# panel446.net
KiCad netlist of a schematic drawn in EAGLE
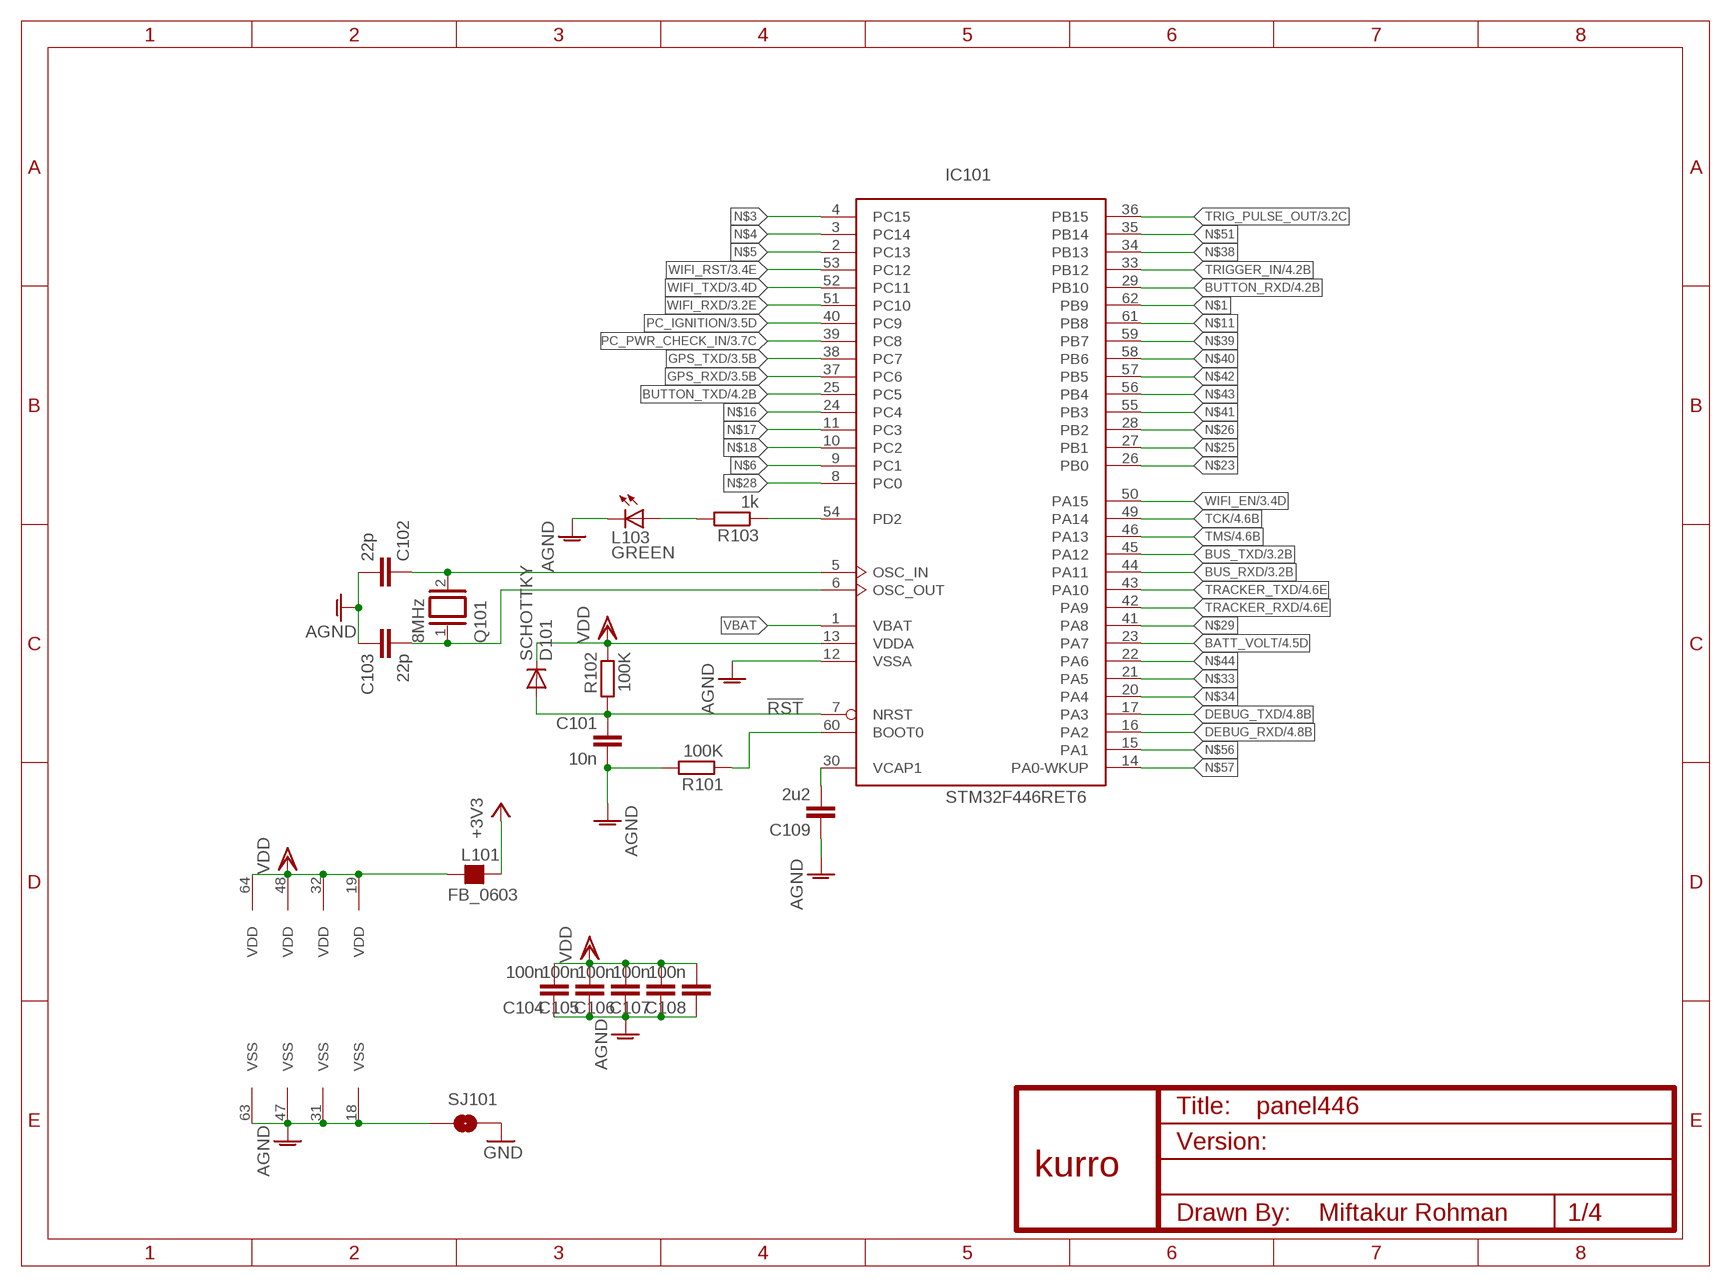
[diagram p0: schematic, sheet 1]
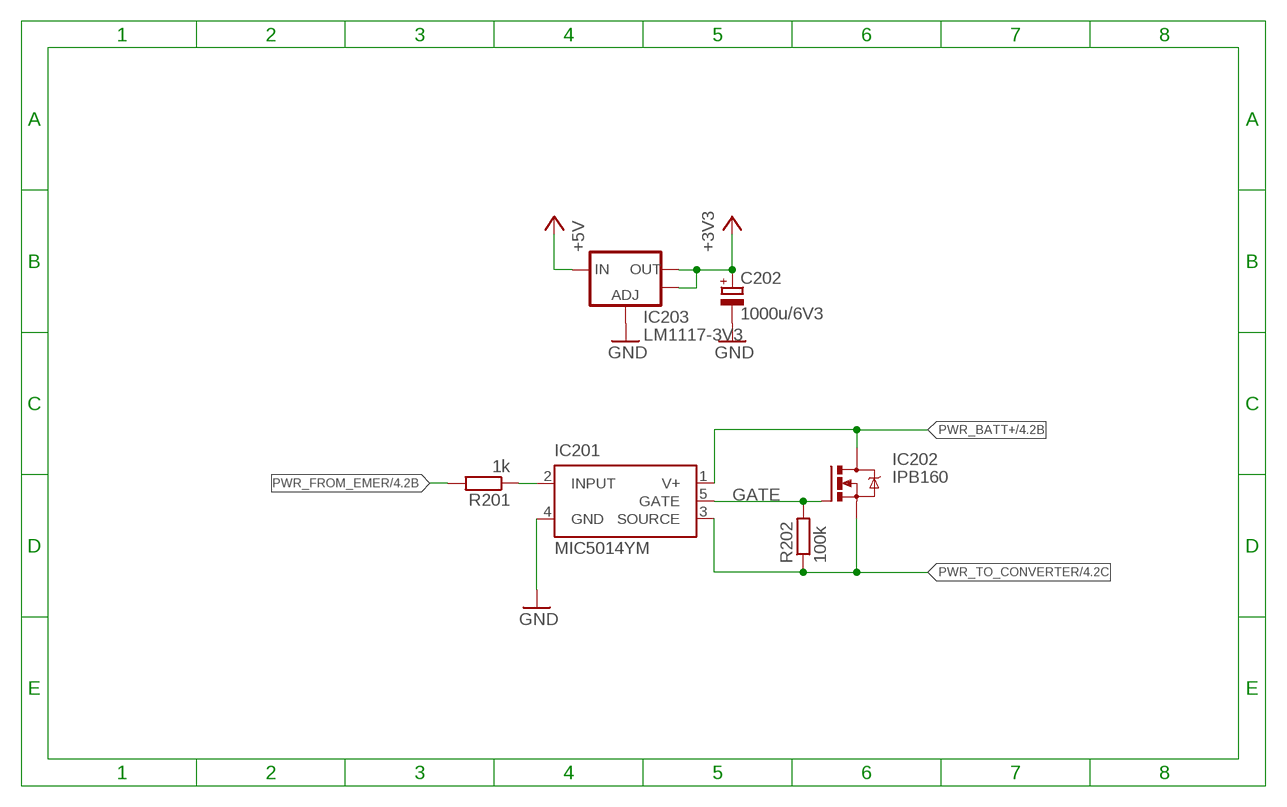
[diagram p1: schematic, sheet 2]
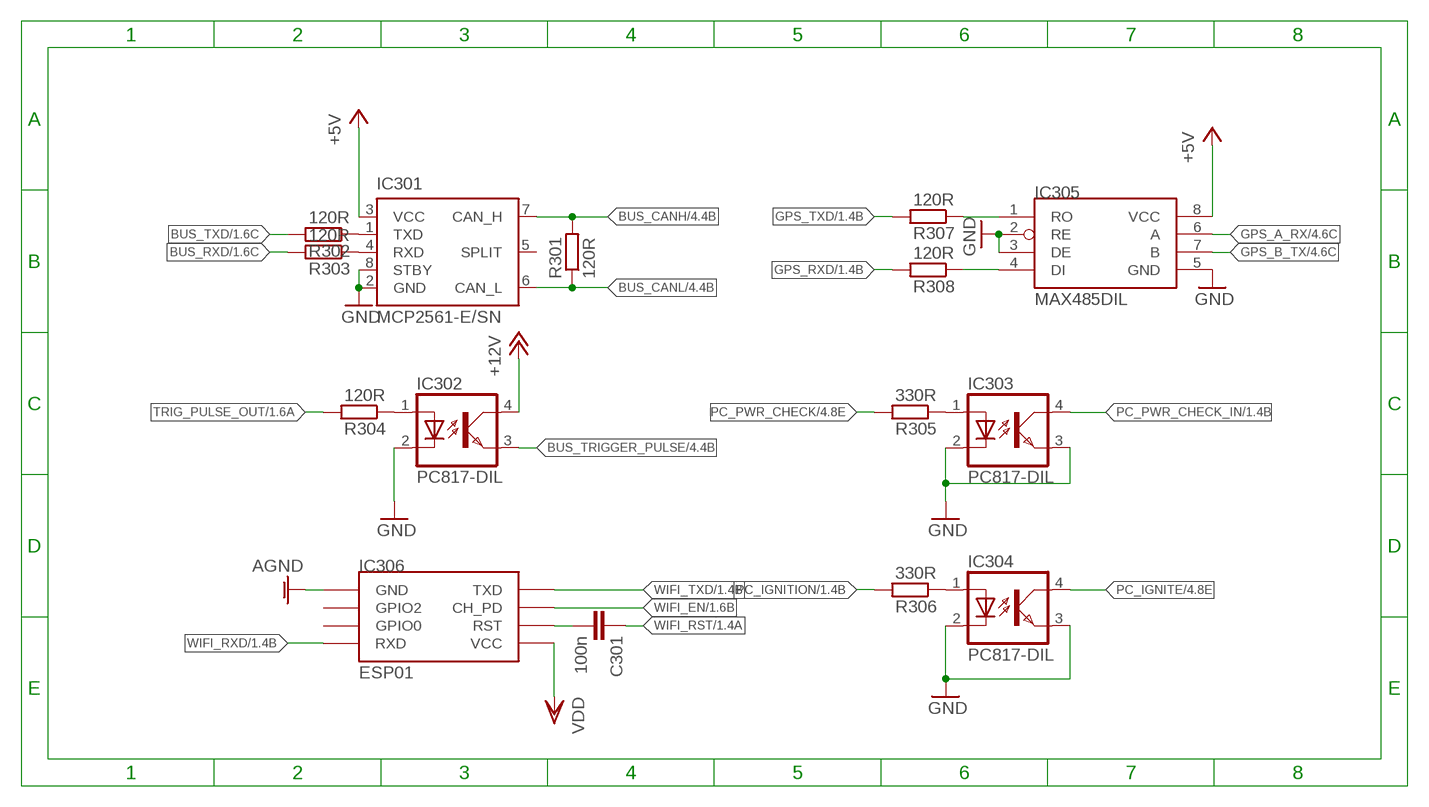
[diagram p2: schematic, sheet 3]
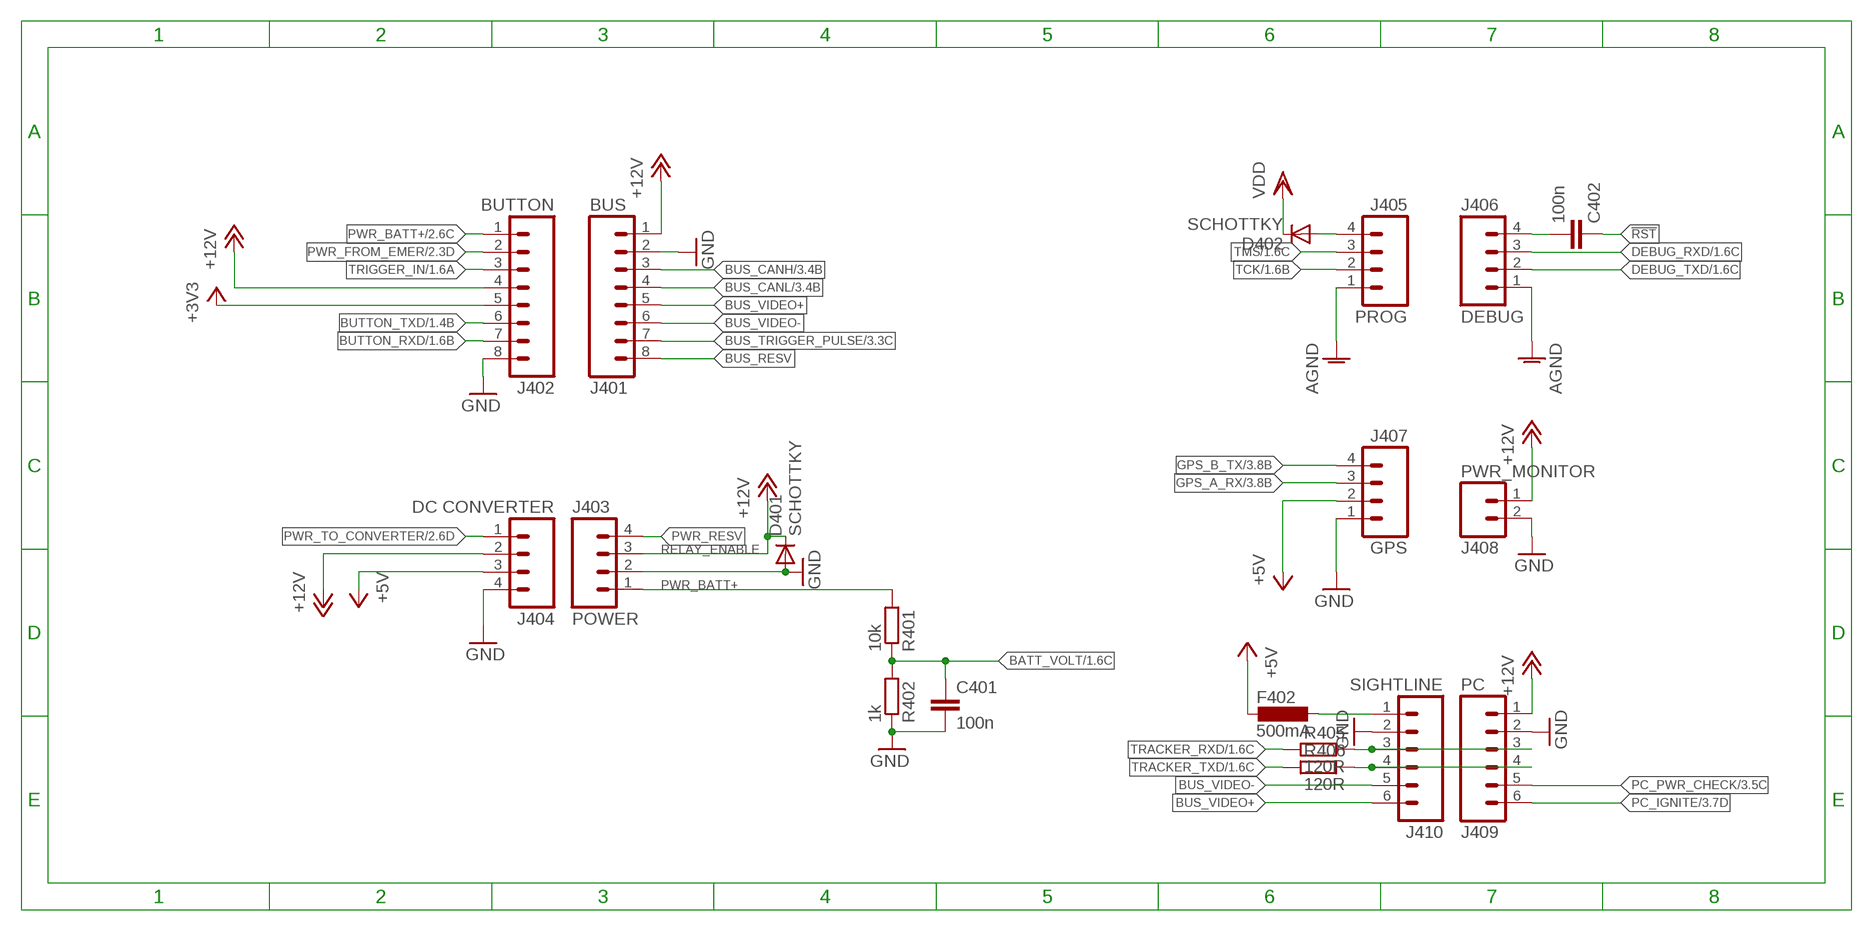
[diagram p3: schematic, sheet 4]

(export (version "E")
  (design (tool "Eeschema 10.0.6"))
  (components
    (comp (ref "C101")
      (value "10n")
      (footprint "eagle-import:C0603")
      (libsource (lib "eagle-import") (part "resistor_C-EUC0603"))
    )
    (comp (ref "C102")
      (value "22p")
      (footprint "eagle-import:C0603")
      (libsource (lib "eagle-import") (part "resistor_C-EUC0603"))
    )
    (comp (ref "C103")
      (value "22p")
      (footprint "eagle-import:C0603")
      (libsource (lib "eagle-import") (part "resistor_C-EUC0603"))
    )
    (comp (ref "C104")
      (value "100n")
      (footprint "eagle-import:C0603")
      (libsource (lib "eagle-import") (part "resistor_C-EUC0603"))
    )
    (comp (ref "C105")
      (value "100n")
      (footprint "eagle-import:C0603")
      (libsource (lib "eagle-import") (part "resistor_C-EUC0603"))
    )
    (comp (ref "C106")
      (value "100n")
      (footprint "eagle-import:C0603")
      (libsource (lib "eagle-import") (part "resistor_C-EUC0603"))
    )
    (comp (ref "C107")
      (value "100n")
      (footprint "eagle-import:C0603")
      (libsource (lib "eagle-import") (part "resistor_C-EUC0603"))
    )
    (comp (ref "C108")
      (value "100n")
      (footprint "eagle-import:C0603")
      (libsource (lib "eagle-import") (part "resistor_C-EUC0603"))
    )
    (comp (ref "C109")
      (value "2u2")
      (footprint "eagle-import:C0805")
      (libsource (lib "eagle-import") (part "C-EUC0805"))
    )
    (comp (ref "D101")
      (value "SCHOTTKY")
      (footprint "eagle-import:MICROMELF-W")
      (libsource (lib "eagle-import") (part "DIODE-MICROMELF-W"))
    )
    (comp (ref "IC101")
      (value "STM32F446RET6")
      (footprint "eagle-import:LQFP64")
      (libsource (lib "eagle-import") (part "STM32F401RTB"))
    )
    (comp (ref "L101")
      (value "FB_0603")
      (footprint "eagle-import:L0603")
      (libsource (lib "eagle-import") (part "FB_0603"))
    )
    (comp (ref "L103")
      (value "GREEN")
      (footprint "eagle-import:CHIP-LED0805")
      (libsource (lib "eagle-import") (part "LEDCHIP-LED0805"))
    )
    (comp (ref "Q101")
      (value "8MHz")
      (footprint "eagle-import:QS")
      (libsource (lib "eagle-import") (part "XTAL/S"))
    )
    (comp (ref "R101")
      (value "100K")
      (footprint "eagle-import:R0603")
      (libsource (lib "eagle-import") (part "resistor_R-EU_R0603"))
    )
    (comp (ref "R102")
      (value "100K")
      (footprint "eagle-import:R0603")
      (libsource (lib "eagle-import") (part "resistor_R-EU_R0603"))
    )
    (comp (ref "R103")
      (value "1k")
      (footprint "eagle-import:R0603")
      (libsource (lib "eagle-import") (part "resistor_R-EU_R0603"))
    )
    (comp (ref "SJ101")
      (value "SOLDERJUMPERTRACE")
      (footprint "eagle-import:SJ_2S-TRACE")
      (libsource (lib "eagle-import") (part "SOLDERJUMPERTRACE"))
    )
    (comp (ref "U$1")
      (value "KURRO_FOOTPRINT")
      (footprint "eagle-import:KURRO-LOGO")
      (libsource (lib "eagle-import") (part "KURRO_FOOTPRINT"))
    )
    (comp (ref "C202")
      (value "1000u/6V3")
      (footprint "eagle-import:153CLV-0810")
      (libsource (lib "eagle-import") (part "CPOL-EU153CLV-0810"))
    )
    (comp (ref "IC201")
      (value "MIC5014YM")
      (footprint "eagle-import:SO-08")
      (libsource (lib "eagle-import") (part "MIC501M4Y"))
    )
    (comp (ref "IC202")
      (value "IPB160")
      (footprint "eagle-import:PG-TO263-7")
      (libsource (lib "eagle-import") (part "IPB160"))
    )
    (comp (ref "IC203")
      (value "LM1117-3V3")
      (footprint "eagle-import:SOT223")
      (libsource (lib "eagle-import") (part "V_REG_LM1117SOT223"))
    )
    (comp (ref "R201")
      (value "1k")
      (footprint "eagle-import:R0603")
      (libsource (lib "eagle-import") (part "R-EU_R0603"))
    )
    (comp (ref "R202")
      (value "100k")
      (footprint "eagle-import:R0603")
      (libsource (lib "eagle-import") (part "R-EU_R0603"))
    )
    (comp (ref "C301")
      (value "100n")
      (footprint "eagle-import:C0603")
      (libsource (lib "eagle-import") (part "resistor_C-EUC0603"))
    )
    (comp (ref "IC301")
      (value "MCP2561-E/SN")
      (footprint "eagle-import:SOIC-8")
      (libsource (lib "eagle-import") (part "MCP2561-E/SN"))
    )
    (comp (ref "IC302")
      (value "PC817-DIL")
      (footprint "eagle-import:DIL04A")
      (libsource (lib "eagle-import") (part "PC817-DIL"))
    )
    (comp (ref "IC303")
      (value "PC817-DIL")
      (footprint "eagle-import:DIL04A")
      (libsource (lib "eagle-import") (part "PC817-DIL"))
    )
    (comp (ref "IC304")
      (value "PC817-DIL")
      (footprint "eagle-import:DIL04A")
      (libsource (lib "eagle-import") (part "PC817-DIL"))
    )
    (comp (ref "IC305")
      (value "MAX485DIL")
      (footprint "eagle-import:DIL08")
      (libsource (lib "eagle-import") (part "MAX485DIL"))
    )
    (comp (ref "IC306")
      (value "ESP01")
      (footprint "eagle-import:ESP01")
      (libsource (lib "eagle-import") (part "ESP01"))
    )
    (comp (ref "R301")
      (value "120R")
      (footprint "eagle-import:R0603")
      (libsource (lib "eagle-import") (part "R-EU_R0603"))
    )
    (comp (ref "R302")
      (value "120R")
      (footprint "eagle-import:R0603")
      (libsource (lib "eagle-import") (part "R-EU_R0603"))
    )
    (comp (ref "R303")
      (value "120R")
      (footprint "eagle-import:R0603")
      (libsource (lib "eagle-import") (part "R-EU_R0603"))
    )
    (comp (ref "R304")
      (value "120R")
      (footprint "eagle-import:R0603")
      (libsource (lib "eagle-import") (part "R-EU_R0603"))
    )
    (comp (ref "R305")
      (value "330R")
      (footprint "eagle-import:R0603")
      (libsource (lib "eagle-import") (part "R-EU_R0603"))
    )
    (comp (ref "R306")
      (value "330R")
      (footprint "eagle-import:R0603")
      (libsource (lib "eagle-import") (part "R-EU_R0603"))
    )
    (comp (ref "R307")
      (value "120R")
      (footprint "eagle-import:R0603")
      (libsource (lib "eagle-import") (part "R-EU_R0603"))
    )
    (comp (ref "R308")
      (value "120R")
      (footprint "eagle-import:R0603")
      (libsource (lib "eagle-import") (part "R-EU_R0603"))
    )
    (comp (ref "C401")
      (value "100n")
      (footprint "eagle-import:C0603")
      (libsource (lib "eagle-import") (part "resistor_C-EUC0603"))
    )
    (comp (ref "C402")
      (value "100n")
      (footprint "eagle-import:C0603")
      (libsource (lib "eagle-import") (part "resistor_C-EUC0603"))
    )
    (comp (ref "D401")
      (value "SCHOTTKY")
      (footprint "eagle-import:MICROMELF-W")
      (libsource (lib "eagle-import") (part "DIODE-MICROMELF-W"))
    )
    (comp (ref "D402")
      (value "SCHOTTKY")
      (footprint "eagle-import:MICROMELF-W")
      (libsource (lib "eagle-import") (part "DIODE-MICROMELF-W"))
    )
    (comp (ref "F402")
      (value "500mA")
      (footprint "eagle-import:L0805")
      (libsource (lib "eagle-import") (part "L-EUL0805"))
    )
    (comp (ref "J401")
      (value "BUS")
      (footprint "eagle-import:XH-8-VERT")
      (libsource (lib "eagle-import") (part "M08-XH-VERT"))
    )
    (comp (ref "J402")
      (value "BUTTON")
      (footprint "eagle-import:XH-8-VERT")
      (libsource (lib "eagle-import") (part "M08-XH-VERT"))
    )
    (comp (ref "J403")
      (value "POWER")
      (footprint "eagle-import:XH-4-VERT")
      (libsource (lib "eagle-import") (part "M04-XH-VERT"))
    )
    (comp (ref "J404")
      (value "DC CONVERTER")
      (footprint "eagle-import:XH-4-VERT")
      (libsource (lib "eagle-import") (part "M04-XH-VERT"))
    )
    (comp (ref "J405")
      (value "PROG")
      (footprint "eagle-import:XH-4-VERT")
      (libsource (lib "eagle-import") (part "M04-XH-VERT"))
    )
    (comp (ref "J406")
      (value "DEBUG")
      (footprint "eagle-import:XH-4-VERT")
      (libsource (lib "eagle-import") (part "M04-XH-VERT"))
    )
    (comp (ref "J407")
      (value "GPS")
      (footprint "eagle-import:XH-4-VERT")
      (libsource (lib "eagle-import") (part "M04-XH-VERT"))
    )
    (comp (ref "J408")
      (value "PWR_MONITOR")
      (footprint "eagle-import:XH-2-RA")
      (libsource (lib "eagle-import") (part "M02-XH-RA"))
    )
    (comp (ref "J409")
      (value "PC")
      (footprint "eagle-import:XH-6-VERT")
      (libsource (lib "eagle-import") (part "M06-XH-VERT"))
    )
    (comp (ref "J410")
      (value "SIGHTLINE")
      (footprint "eagle-import:XH-6-VERT")
      (libsource (lib "eagle-import") (part "M06-XH-VERT"))
    )
    (comp (ref "R401")
      (value "10k")
      (footprint "eagle-import:R0603")
      (libsource (lib "eagle-import") (part "R-EU_R0603"))
    )
    (comp (ref "R402")
      (value "1k")
      (footprint "eagle-import:R0603")
      (libsource (lib "eagle-import") (part "R-EU_R0603"))
    )
    (comp (ref "R405")
      (value "120R")
      (footprint "eagle-import:R0603")
      (libsource (lib "eagle-import") (part "R-EU_R0603"))
    )
    (comp (ref "R406")
      (value "120R")
      (footprint "eagle-import:R0603")
      (libsource (lib "eagle-import") (part "R-EU_R0603"))
    )
  )
  (nets
    (net (code "1") (name "+3V3") (class "Default")
      (node (ref "C202") (pin "+") (pinfunction "+_+") (pintype "passive"))
      (node (ref "IC203") (pin "2") (pinfunction "OUT_2") (pintype "power_in"))
      (node (ref "IC203") (pin "4") (pinfunction "OUT_4") (pintype "power_in"))
      (node (ref "J402") (pin "5") (pinfunction "5_5") (pintype "passive"))
      (node (ref "L101") (pin "2") (pinfunction "2_2") (pintype "passive"))
    )
    (net (code "2") (name "+5V") (class "Default")
      (node (ref "F402") (pin "2") (pinfunction "2_2") (pintype "passive"))
      (node (ref "IC203") (pin "3") (pinfunction "IN_3") (pintype "input"))
      (node (ref "IC301") (pin "3") (pinfunction "VCC_3") (pintype "bidirectional"))
      (node (ref "IC305") (pin "8") (pinfunction "VCC_8") (pintype "bidirectional"))
      (node (ref "J404") (pin "3") (pinfunction "3_3") (pintype "passive"))
      (node (ref "J407") (pin "2") (pinfunction "2_2") (pintype "passive"))
    )
    (net (code "3") (name "+12V") (class "Default")
      (node (ref "D401") (pin "C") (pinfunction "C_C") (pintype "passive"))
      (node (ref "IC302") (pin "4") (pinfunction "COL_4") (pintype "passive"))
      (node (ref "J401") (pin "1") (pinfunction "1_1") (pintype "passive"))
      (node (ref "J402") (pin "4") (pinfunction "4_4") (pintype "passive"))
      (node (ref "J403") (pin "3") (pinfunction "3_3") (pintype "passive"))
      (node (ref "J404") (pin "2") (pinfunction "2_2") (pintype "passive"))
      (node (ref "J408") (pin "1") (pinfunction "1_1") (pintype "passive"))
      (node (ref "J409") (pin "1") (pinfunction "1_1") (pintype "passive"))
    )
    (net (code "4") (name "AGND") (class "Default")
      (node (ref "C101") (pin "2") (pinfunction "2_2") (pintype "passive"))
      (node (ref "C102") (pin "2") (pinfunction "2_2") (pintype "passive"))
      (node (ref "C103") (pin "1") (pinfunction "1_1") (pintype "passive"))
      (node (ref "C104") (pin "1") (pinfunction "1_1") (pintype "passive"))
      (node (ref "C105") (pin "1") (pinfunction "1_1") (pintype "passive"))
      (node (ref "C106") (pin "1") (pinfunction "1_1") (pintype "passive"))
      (node (ref "C107") (pin "1") (pinfunction "1_1") (pintype "passive"))
      (node (ref "C108") (pin "1") (pinfunction "1_1") (pintype "passive"))
      (node (ref "C109") (pin "1") (pinfunction "1_1") (pintype "passive"))
      (node (ref "IC101") (pin "12") (pinfunction "VSSA_12") (pintype "power_in"))
      (node (ref "IC101") (pin "18") (pinfunction "VSS_18") (pintype "power_in"))
      (node (ref "IC101") (pin "31") (pinfunction "VSS_31") (pintype "power_in"))
      (node (ref "IC101") (pin "47") (pinfunction "VSS_47") (pintype "power_in"))
      (node (ref "IC101") (pin "63") (pinfunction "VSS_63") (pintype "power_in"))
      (node (ref "IC306") (pin "GND") (pinfunction "GND_GND") (pintype "bidirectional"))
      (node (ref "J405") (pin "1") (pinfunction "1_1") (pintype "passive"))
      (node (ref "J406") (pin "1") (pinfunction "1_1") (pintype "passive"))
      (node (ref "L103") (pin "C") (pinfunction "C_C") (pintype "passive"))
      (node (ref "R101") (pin "2") (pinfunction "2_2") (pintype "passive"))
      (node (ref "SJ101") (pin "1") (pinfunction "1_1") (pintype "passive"))
    )
    (net (code "5") (name "BATT_VOLT") (class "Default")
      (node (ref "C401") (pin "1") (pinfunction "1_1") (pintype "passive"))
      (node (ref "IC101") (pin "23") (pinfunction "PA7_23") (pintype "bidirectional"))
      (node (ref "R401") (pin "1") (pinfunction "1_1") (pintype "passive"))
      (node (ref "R402") (pin "2") (pinfunction "2_2") (pintype "passive"))
    )
    (net (code "6") (name "BUS_CANH") (class "Default")
      (node (ref "IC301") (pin "7") (pinfunction "CAN_H_7") (pintype "bidirectional"))
      (node (ref "J401") (pin "3") (pinfunction "3_3") (pintype "passive"))
      (node (ref "R301") (pin "2") (pinfunction "2_2") (pintype "passive"))
    )
    (net (code "7") (name "BUS_CANL") (class "Default")
      (node (ref "IC301") (pin "6") (pinfunction "CAN_L_6") (pintype "bidirectional"))
      (node (ref "J401") (pin "4") (pinfunction "4_4") (pintype "passive"))
      (node (ref "R301") (pin "1") (pinfunction "1_1") (pintype "passive"))
    )
    (net (code "8") (name "BUS_RESV") (class "Default")
      (node (ref "J401") (pin "8") (pinfunction "8_8") (pintype "passive"))
    )
    (net (code "9") (name "BUS_RXD") (class "Default")
      (node (ref "IC101") (pin "44") (pinfunction "PA11_44") (pintype "bidirectional"))
      (node (ref "R303") (pin "2") (pinfunction "2_2") (pintype "passive"))
    )
    (net (code "10") (name "BUS_TRIGGER_PULSE") (class "Default")
      (node (ref "IC302") (pin "3") (pinfunction "EMIT_3") (pintype "passive"))
      (node (ref "J401") (pin "7") (pinfunction "7_7") (pintype "passive"))
    )
    (net (code "11") (name "BUS_TXD") (class "Default")
      (node (ref "IC101") (pin "45") (pinfunction "PA12_45") (pintype "bidirectional"))
      (node (ref "R302") (pin "2") (pinfunction "2_2") (pintype "passive"))
    )
    (net (code "12") (name "BUS_VIDEO+") (class "Default")
      (node (ref "J401") (pin "5") (pinfunction "5_5") (pintype "passive"))
      (node (ref "J410") (pin "6") (pinfunction "6_6") (pintype "passive"))
    )
    (net (code "13") (name "BUS_VIDEO-") (class "Default")
      (node (ref "J401") (pin "6") (pinfunction "6_6") (pintype "passive"))
      (node (ref "J410") (pin "5") (pinfunction "5_5") (pintype "passive"))
    )
    (net (code "14") (name "BUTTON_RXD") (class "Default")
      (node (ref "IC101") (pin "29") (pinfunction "PB10_29") (pintype "bidirectional"))
      (node (ref "J402") (pin "7") (pinfunction "7_7") (pintype "passive"))
    )
    (net (code "15") (name "BUTTON_TXD") (class "Default")
      (node (ref "IC101") (pin "25") (pinfunction "PC5_25") (pintype "bidirectional"))
      (node (ref "J402") (pin "6") (pinfunction "6_6") (pintype "passive"))
    )
    (net (code "16") (name "DEBUG_RXD") (class "Default")
      (node (ref "IC101") (pin "16") (pinfunction "PA2_16") (pintype "bidirectional"))
      (node (ref "J406") (pin "3") (pinfunction "3_3") (pintype "passive"))
    )
    (net (code "17") (name "DEBUG_TXD") (class "Default")
      (node (ref "IC101") (pin "17") (pinfunction "PA3_17") (pintype "bidirectional"))
      (node (ref "J406") (pin "2") (pinfunction "2_2") (pintype "passive"))
    )
    (net (code "18") (name "GATE") (class "Default")
      (node (ref "IC201") (pin "5") (pinfunction "GATE_5") (pintype "bidirectional"))
      (node (ref "IC202") (pin "1") (pinfunction "G_1") (pintype "passive"))
      (node (ref "R202") (pin "2") (pinfunction "2_2") (pintype "passive"))
    )
    (net (code "19") (name "GND") (class "Default")
      (node (ref "C202") (pin "-") (pinfunction "-_-") (pintype "passive"))
      (node (ref "C401") (pin "2") (pinfunction "2_2") (pintype "passive"))
      (node (ref "D401") (pin "A") (pinfunction "A_A") (pintype "passive"))
      (node (ref "IC201") (pin "4") (pinfunction "GND_4") (pintype "bidirectional"))
      (node (ref "IC203") (pin "1") (pinfunction "ADJ_1") (pintype "input"))
      (node (ref "IC301") (pin "2") (pinfunction "GND_2") (pintype "bidirectional"))
      (node (ref "IC301") (pin "8") (pinfunction "STBY_8") (pintype "bidirectional"))
      (node (ref "IC302") (pin "2") (pinfunction "C_2") (pintype "passive"))
      (node (ref "IC303") (pin "2") (pinfunction "C_2") (pintype "passive"))
      (node (ref "IC303") (pin "3") (pinfunction "EMIT_3") (pintype "passive"))
      (node (ref "IC304") (pin "2") (pinfunction "C_2") (pintype "passive"))
      (node (ref "IC304") (pin "3") (pinfunction "EMIT_3") (pintype "passive"))
      (node (ref "IC305") (pin "2") (pinfunction "RE_2") (pintype "bidirectional"))
      (node (ref "IC305") (pin "3") (pinfunction "DE_3") (pintype "bidirectional"))
      (node (ref "IC305") (pin "5") (pinfunction "GND_5") (pintype "bidirectional"))
      (node (ref "J401") (pin "2") (pinfunction "2_2") (pintype "passive"))
      (node (ref "J402") (pin "8") (pinfunction "8_8") (pintype "passive"))
      (node (ref "J403") (pin "2") (pinfunction "2_2") (pintype "passive"))
      (node (ref "J404") (pin "4") (pinfunction "4_4") (pintype "passive"))
      (node (ref "J407") (pin "1") (pinfunction "1_1") (pintype "passive"))
      (node (ref "J408") (pin "2") (pinfunction "2_2") (pintype "passive"))
      (node (ref "J409") (pin "2") (pinfunction "2_2") (pintype "passive"))
      (node (ref "J410") (pin "2") (pinfunction "2_2") (pintype "passive"))
      (node (ref "R402") (pin "1") (pinfunction "1_1") (pintype "passive"))
      (node (ref "SJ101") (pin "2") (pinfunction "2_2") (pintype "passive"))
    )
    (net (code "20") (name "GPS_A_RX") (class "Default")
      (node (ref "IC305") (pin "6") (pinfunction "A_6") (pintype "bidirectional"))
      (node (ref "J407") (pin "3") (pinfunction "3_3") (pintype "passive"))
    )
    (net (code "21") (name "GPS_B_TX") (class "Default")
      (node (ref "IC305") (pin "7") (pinfunction "B_7") (pintype "bidirectional"))
      (node (ref "J407") (pin "4") (pinfunction "4_4") (pintype "passive"))
    )
    (net (code "22") (name "GPS_RXD") (class "Default")
      (node (ref "IC101") (pin "37") (pinfunction "PC6_37") (pintype "bidirectional"))
      (node (ref "R308") (pin "2") (pinfunction "2_2") (pintype "passive"))
    )
    (net (code "23") (name "GPS_TXD") (class "Default")
      (node (ref "IC101") (pin "38") (pinfunction "PC7_38") (pintype "bidirectional"))
      (node (ref "R307") (pin "2") (pinfunction "2_2") (pintype "passive"))
    )
    (net (code "24") (name "N$1") (class "Default")
      (node (ref "IC101") (pin "62") (pinfunction "PB9_62") (pintype "bidirectional"))
    )
    (net (code "25") (name "N$3") (class "Default")
      (node (ref "IC101") (pin "4") (pinfunction "PC15_4") (pintype "bidirectional"))
    )
    (net (code "26") (name "N$4") (class "Default")
      (node (ref "IC101") (pin "3") (pinfunction "PC14_3") (pintype "bidirectional"))
    )
    (net (code "27") (name "N$5") (class "Default")
      (node (ref "IC101") (pin "2") (pinfunction "PC13_2") (pintype "bidirectional"))
    )
    (net (code "28") (name "N$6") (class "Default")
      (node (ref "IC101") (pin "9") (pinfunction "PC1_9") (pintype "bidirectional"))
    )
    (net (code "29") (name "N$11") (class "Default")
      (node (ref "IC101") (pin "61") (pinfunction "PB8_61") (pintype "bidirectional"))
    )
    (net (code "30") (name "N$16") (class "Default")
      (node (ref "IC101") (pin "24") (pinfunction "PC4_24") (pintype "bidirectional"))
    )
    (net (code "31") (name "N$17") (class "Default")
      (node (ref "IC101") (pin "11") (pinfunction "PC3_11") (pintype "bidirectional"))
    )
    (net (code "32") (name "N$18") (class "Default")
      (node (ref "IC101") (pin "10") (pinfunction "PC2_10") (pintype "bidirectional"))
    )
    (net (code "33") (name "N$23") (class "Default")
      (node (ref "IC101") (pin "26") (pinfunction "PB0_26") (pintype "bidirectional"))
    )
    (net (code "34") (name "N$25") (class "Default")
      (node (ref "IC101") (pin "27") (pinfunction "PB1_27") (pintype "bidirectional"))
    )
    (net (code "35") (name "N$26") (class "Default")
      (node (ref "IC101") (pin "28") (pinfunction "PB2_28") (pintype "bidirectional"))
    )
    (net (code "36") (name "N$28") (class "Default")
      (node (ref "IC101") (pin "8") (pinfunction "PC0_8") (pintype "bidirectional"))
    )
    (net (code "37") (name "N$29") (class "Default")
      (node (ref "IC101") (pin "41") (pinfunction "PA8_41") (pintype "bidirectional"))
    )
    (net (code "38") (name "N$33") (class "Default")
      (node (ref "IC101") (pin "21") (pinfunction "PA5_21") (pintype "bidirectional"))
    )
    (net (code "39") (name "N$34") (class "Default")
      (node (ref "IC101") (pin "20") (pinfunction "PA4_20") (pintype "bidirectional"))
    )
    (net (code "40") (name "N$38") (class "Default")
      (node (ref "IC101") (pin "34") (pinfunction "PB13_34") (pintype "bidirectional"))
    )
    (net (code "41") (name "N$39") (class "Default")
      (node (ref "IC101") (pin "59") (pinfunction "PB7_59") (pintype "bidirectional"))
    )
    (net (code "42") (name "N$40") (class "Default")
      (node (ref "IC101") (pin "58") (pinfunction "PB6_58") (pintype "bidirectional"))
    )
    (net (code "43") (name "N$41") (class "Default")
      (node (ref "IC101") (pin "55") (pinfunction "PB3_55") (pintype "bidirectional"))
    )
    (net (code "44") (name "N$42") (class "Default")
      (node (ref "IC101") (pin "57") (pinfunction "PB5_57") (pintype "bidirectional"))
    )
    (net (code "45") (name "N$43") (class "Default")
      (node (ref "IC101") (pin "56") (pinfunction "PB4_56") (pintype "bidirectional"))
    )
    (net (code "46") (name "N$44") (class "Default")
      (node (ref "IC101") (pin "22") (pinfunction "PA6_22") (pintype "bidirectional"))
    )
    (net (code "47") (name "N$51") (class "Default")
      (node (ref "IC101") (pin "35") (pinfunction "PB14_35") (pintype "bidirectional"))
    )
    (net (code "48") (name "N$56") (class "Default")
      (node (ref "IC101") (pin "15") (pinfunction "PA1_15") (pintype "bidirectional"))
    )
    (net (code "49") (name "N$57") (class "Default")
      (node (ref "IC101") (pin "14") (pinfunction "PA0-WKUP_14") (pintype "bidirectional"))
    )
    (net (code "50") (name "Net-(C301-Pad2)") (class "Default")
      (node (ref "C301") (pin "2") (pinfunction "2_2") (pintype "passive"))
      (node (ref "IC306") (pin "RST") (pinfunction "RST_RST") (pintype "bidirectional"))
    )
    (net (code "51") (name "Net-(C402-Pad2)") (class "Default")
      (node (ref "C402") (pin "2") (pinfunction "2_2") (pintype "passive"))
      (node (ref "J406") (pin "4") (pinfunction "4_4") (pintype "passive"))
    )
    (net (code "52") (name "Net-(D402-PadA)") (class "Default")
      (node (ref "D402") (pin "A") (pinfunction "A_A") (pintype "passive"))
      (node (ref "J405") (pin "4") (pinfunction "4_4") (pintype "passive"))
    )
    (net (code "53") (name "Net-(F402-Pad1)") (class "Default")
      (node (ref "F402") (pin "1") (pinfunction "1_1") (pintype "passive"))
      (node (ref "J410") (pin "1") (pinfunction "1_1") (pintype "passive"))
    )
    (net (code "54") (name "Net-(IC101A-BOOT0)") (class "Default")
      (node (ref "IC101") (pin "60") (pinfunction "BOOT0_60") (pintype "input"))
      (node (ref "R101") (pin "1") (pinfunction "1_1") (pintype "passive"))
    )
    (net (code "55") (name "Net-(IC101A-OSC_IN)") (class "Default")
      (node (ref "C102") (pin "1") (pinfunction "1_1") (pintype "passive"))
      (node (ref "IC101") (pin "5") (pinfunction "OSC_IN_5") (pintype "bidirectional"))
      (node (ref "Q101") (pin "2") (pinfunction "2_2") (pintype "passive"))
    )
    (net (code "56") (name "Net-(IC101A-OSC_OUT)") (class "Default")
      (node (ref "C103") (pin "2") (pinfunction "2_2") (pintype "passive"))
      (node (ref "IC101") (pin "6") (pinfunction "OSC_OUT_6") (pintype "bidirectional"))
      (node (ref "Q101") (pin "1") (pinfunction "1_1") (pintype "passive"))
    )
    (net (code "57") (name "Net-(IC101A-PD2)") (class "Default")
      (node (ref "IC101") (pin "54") (pinfunction "PD2_54") (pintype "bidirectional"))
      (node (ref "R103") (pin "1") (pinfunction "1_1") (pintype "passive"))
    )
    (net (code "58") (name "Net-(IC101A-VCAP1)") (class "Default")
      (node (ref "C109") (pin "2") (pinfunction "2_2") (pintype "passive"))
      (node (ref "IC101") (pin "30") (pinfunction "VCAP1_30") (pintype "power_in"))
    )
    (net (code "59") (name "Net-(IC201-INPUT)") (class "Default")
      (node (ref "IC201") (pin "2") (pinfunction "INPUT_2") (pintype "bidirectional"))
      (node (ref "R201") (pin "1") (pinfunction "1_1") (pintype "passive"))
    )
    (net (code "60") (name "Net-(IC301-RXD)") (class "Default")
      (node (ref "IC301") (pin "4") (pinfunction "RXD_4") (pintype "bidirectional"))
      (node (ref "R303") (pin "1") (pinfunction "1_1") (pintype "passive"))
    )
    (net (code "61") (name "Net-(IC301-TXD)") (class "Default")
      (node (ref "IC301") (pin "1") (pinfunction "TXD_1") (pintype "bidirectional"))
      (node (ref "R302") (pin "1") (pinfunction "1_1") (pintype "passive"))
    )
    (net (code "62") (name "Net-(IC302-A)") (class "Default")
      (node (ref "IC302") (pin "1") (pinfunction "A_1") (pintype "passive"))
      (node (ref "R304") (pin "1") (pinfunction "1_1") (pintype "passive"))
    )
    (net (code "63") (name "Net-(IC303-A)") (class "Default")
      (node (ref "IC303") (pin "1") (pinfunction "A_1") (pintype "passive"))
      (node (ref "R305") (pin "1") (pinfunction "1_1") (pintype "passive"))
    )
    (net (code "64") (name "Net-(IC304-A)") (class "Default")
      (node (ref "IC304") (pin "1") (pinfunction "A_1") (pintype "passive"))
      (node (ref "R306") (pin "1") (pinfunction "1_1") (pintype "passive"))
    )
    (net (code "65") (name "Net-(IC305-DI)") (class "Default")
      (node (ref "IC305") (pin "4") (pinfunction "DI_4") (pintype "bidirectional"))
      (node (ref "R308") (pin "1") (pinfunction "1_1") (pintype "passive"))
    )
    (net (code "66") (name "Net-(IC305-RO)") (class "Default")
      (node (ref "IC305") (pin "1") (pinfunction "RO_1") (pintype "bidirectional"))
      (node (ref "R307") (pin "1") (pinfunction "1_1") (pintype "passive"))
    )
    (net (code "67") (name "Net-(J409-Pad3)") (class "Default")
      (node (ref "J409") (pin "3") (pinfunction "3_3") (pintype "passive"))
      (node (ref "J410") (pin "3") (pinfunction "3_3") (pintype "passive"))
      (node (ref "R405") (pin "1") (pinfunction "1_1") (pintype "passive"))
    )
    (net (code "68") (name "Net-(J409-Pad4)") (class "Default")
      (node (ref "J409") (pin "4") (pinfunction "4_4") (pintype "passive"))
      (node (ref "J410") (pin "4") (pinfunction "4_4") (pintype "passive"))
      (node (ref "R406") (pin "1") (pinfunction "1_1") (pintype "passive"))
    )
    (net (code "69") (name "Net-(L103-PadA)") (class "Default")
      (node (ref "L103") (pin "A") (pinfunction "A_A") (pintype "passive"))
      (node (ref "R103") (pin "2") (pinfunction "2_2") (pintype "passive"))
    )
    (net (code "70") (name "PC_IGNITE") (class "Default")
      (node (ref "IC304") (pin "4") (pinfunction "COL_4") (pintype "passive"))
      (node (ref "J409") (pin "6") (pinfunction "6_6") (pintype "passive"))
    )
    (net (code "71") (name "PC_IGNITION") (class "Default")
      (node (ref "IC101") (pin "40") (pinfunction "PC9_40") (pintype "bidirectional"))
      (node (ref "R306") (pin "2") (pinfunction "2_2") (pintype "passive"))
    )
    (net (code "72") (name "PC_PWR_CHECK") (class "Default")
      (node (ref "J409") (pin "5") (pinfunction "5_5") (pintype "passive"))
      (node (ref "R305") (pin "2") (pinfunction "2_2") (pintype "passive"))
    )
    (net (code "73") (name "PC_PWR_CHECK_IN") (class "Default")
      (node (ref "IC101") (pin "39") (pinfunction "PC8_39") (pintype "bidirectional"))
      (node (ref "IC303") (pin "4") (pinfunction "COL_4") (pintype "passive"))
    )
    (net (code "74") (name "PWR_BATT+") (class "Default")
      (node (ref "IC201") (pin "1") (pinfunction "V+_1") (pintype "bidirectional"))
      (node (ref "IC202") (pin "4") (pinfunction "D_4") (pintype "passive"))
      (node (ref "J402") (pin "1") (pinfunction "1_1") (pintype "passive"))
      (node (ref "J403") (pin "1") (pinfunction "1_1") (pintype "passive"))
      (node (ref "R401") (pin "2") (pinfunction "2_2") (pintype "passive"))
    )
    (net (code "75") (name "PWR_FROM_EMER") (class "Default")
      (node (ref "J402") (pin "2") (pinfunction "2_2") (pintype "passive"))
      (node (ref "R201") (pin "2") (pinfunction "2_2") (pintype "passive"))
    )
    (net (code "76") (name "PWR_RESV") (class "Default")
      (node (ref "J403") (pin "4") (pinfunction "4_4") (pintype "passive"))
    )
    (net (code "77") (name "PWR_TO_CONVERTER") (class "Default")
      (node (ref "IC201") (pin "3") (pinfunction "SOURCE_3") (pintype "bidirectional"))
      (node (ref "IC202") (pin "2") (pinfunction "S_2") (pintype "passive"))
      (node (ref "IC202") (pin "3") (pinfunction "S_3") (pintype "passive"))
      (node (ref "IC202") (pin "5") (pinfunction "S_5") (pintype "passive"))
      (node (ref "IC202") (pin "6") (pinfunction "S_6") (pintype "passive"))
      (node (ref "IC202") (pin "7") (pinfunction "S_7") (pintype "passive"))
      (node (ref "J404") (pin "1") (pinfunction "1_1") (pintype "passive"))
      (node (ref "R202") (pin "1") (pinfunction "1_1") (pintype "passive"))
    )
    (net (code "78") (name "TCK") (class "Default")
      (node (ref "IC101") (pin "49") (pinfunction "PA14_49") (pintype "bidirectional"))
      (node (ref "J405") (pin "2") (pinfunction "2_2") (pintype "passive"))
    )
    (net (code "79") (name "TMS") (class "Default")
      (node (ref "IC101") (pin "46") (pinfunction "PA13_46") (pintype "bidirectional"))
      (node (ref "J405") (pin "3") (pinfunction "3_3") (pintype "passive"))
    )
    (net (code "80") (name "TRACKER_RXD") (class "Default")
      (node (ref "IC101") (pin "42") (pinfunction "PA9_42") (pintype "bidirectional"))
      (node (ref "R405") (pin "2") (pinfunction "2_2") (pintype "passive"))
    )
    (net (code "81") (name "TRACKER_TXD") (class "Default")
      (node (ref "IC101") (pin "43") (pinfunction "PA10_43") (pintype "bidirectional"))
      (node (ref "R406") (pin "2") (pinfunction "2_2") (pintype "passive"))
    )
    (net (code "82") (name "TRIGGER_IN") (class "Default")
      (node (ref "IC101") (pin "33") (pinfunction "PB12_33") (pintype "bidirectional"))
      (node (ref "J402") (pin "3") (pinfunction "3_3") (pintype "passive"))
    )
    (net (code "83") (name "TRIG_PULSE_OUT") (class "Default")
      (node (ref "IC101") (pin "36") (pinfunction "PB15_36") (pintype "bidirectional"))
      (node (ref "R304") (pin "2") (pinfunction "2_2") (pintype "passive"))
    )
    (net (code "84") (name "VBAT") (class "Default")
      (node (ref "IC101") (pin "1") (pinfunction "VBAT_1") (pintype "power_in"))
    )
    (net (code "85") (name "VDD") (class "Default")
      (node (ref "C104") (pin "2") (pinfunction "2_2") (pintype "passive"))
      (node (ref "C105") (pin "2") (pinfunction "2_2") (pintype "passive"))
      (node (ref "C106") (pin "2") (pinfunction "2_2") (pintype "passive"))
      (node (ref "C107") (pin "2") (pinfunction "2_2") (pintype "passive"))
      (node (ref "C108") (pin "2") (pinfunction "2_2") (pintype "passive"))
      (node (ref "D101") (pin "C") (pinfunction "C_C") (pintype "passive"))
      (node (ref "D402") (pin "C") (pinfunction "C_C") (pintype "passive"))
      (node (ref "IC101") (pin "13") (pinfunction "VDDA_13") (pintype "power_in"))
      (node (ref "IC101") (pin "19") (pinfunction "VDD_19") (pintype "power_in"))
      (node (ref "IC101") (pin "32") (pinfunction "VDD_32") (pintype "power_in"))
      (node (ref "IC101") (pin "48") (pinfunction "VDD_48") (pintype "power_in"))
      (node (ref "IC101") (pin "64") (pinfunction "VDD_64") (pintype "power_in"))
      (node (ref "IC306") (pin "VCC") (pinfunction "VCC_VCC") (pintype "bidirectional"))
      (node (ref "L101") (pin "1") (pinfunction "1_1") (pintype "passive"))
      (node (ref "R102") (pin "1") (pinfunction "1_1") (pintype "passive"))
    )
    (net (code "86") (name "WIFI_EN") (class "Default")
      (node (ref "IC101") (pin "50") (pinfunction "PA15_50") (pintype "bidirectional"))
      (node (ref "IC306") (pin "CH_PD") (pinfunction "CH_PD_CH_PD") (pintype "bidirectional"))
    )
    (net (code "87") (name "WIFI_RST") (class "Default")
      (node (ref "C301") (pin "1") (pinfunction "1_1") (pintype "passive"))
      (node (ref "IC101") (pin "53") (pinfunction "PC12_53") (pintype "bidirectional"))
    )
    (net (code "88") (name "WIFI_RXD") (class "Default")
      (node (ref "IC101") (pin "51") (pinfunction "PC10_51") (pintype "bidirectional"))
      (node (ref "IC306") (pin "RX") (pinfunction "RXD_RX") (pintype "bidirectional"))
    )
    (net (code "89") (name "WIFI_TXD") (class "Default")
      (node (ref "IC101") (pin "52") (pinfunction "PC11_52") (pintype "bidirectional"))
      (node (ref "IC306") (pin "TX") (pinfunction "TXD_TX") (pintype "bidirectional"))
    )
    (net (code "90") (name "unconnected-(IC301-SPLIT-Pad5)") (class "Default")
      (node (ref "IC301") (pin "5") (pinfunction "SPLIT_5") (pintype "bidirectional"))
    )
    (net (code "91") (name "unconnected-(IC306-PadGPIO0)") (class "Default")
      (node (ref "IC306") (pin "GPIO0") (pinfunction "GPIO0_GPIO0") (pintype "bidirectional"))
    )
    (net (code "92") (name "unconnected-(IC306-PadGPIO2)") (class "Default")
      (node (ref "IC306") (pin "GPIO2") (pinfunction "GPIO2_GPIO2") (pintype "bidirectional"))
    )
    (net (code "93") (name "~{RST}") (class "Default")
      (node (ref "C101") (pin "1") (pinfunction "1_1") (pintype "passive"))
      (node (ref "C402") (pin "1") (pinfunction "1_1") (pintype "passive"))
      (node (ref "D101") (pin "A") (pinfunction "A_A") (pintype "passive"))
      (node (ref "IC101") (pin "7") (pinfunction "NRST_7") (pintype "bidirectional"))
      (node (ref "R102") (pin "2") (pinfunction "2_2") (pintype "passive"))
    )
  )
)
